# TriDrone_mini_v1.net
KiCad netlist of a schematic drawn in EAGLE
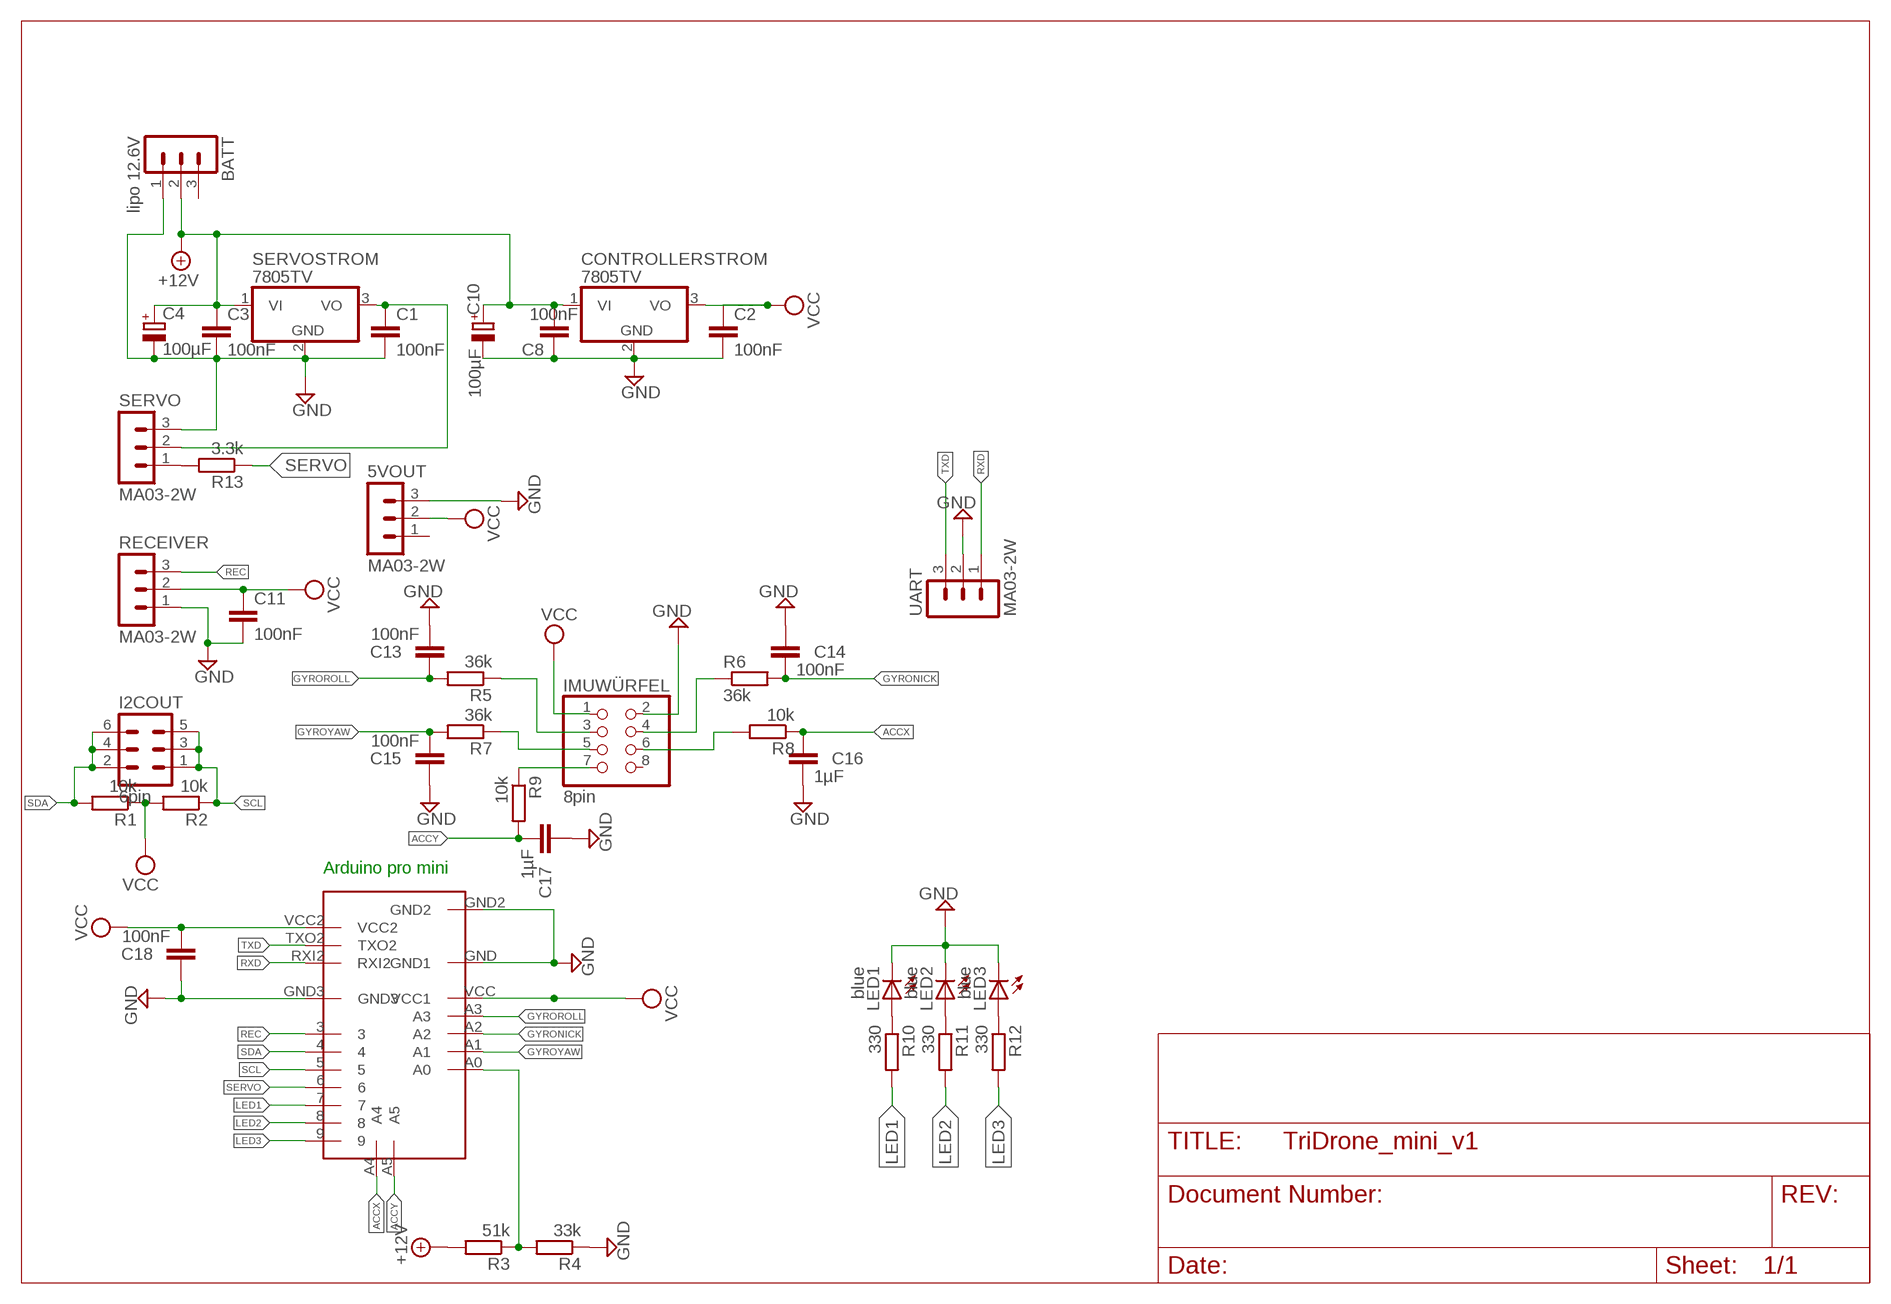
[diagram p0: schematic, sheet 1]

(export (version "E")
  (design (tool "Eeschema 10.0.6"))
  (components
    (comp (ref "5VOUT")
      (value "MA03-2W")
      (footprint "eagle-import:MA03-1")
      (libsource (lib "eagle-import") (part "MA03-1"))
    )
    (comp (ref "BATT")
      (value "lipo 12.6V")
      (footprint "eagle-import:MA03-1")
      (libsource (lib "eagle-import") (part "MA03-1"))
    )
    (comp (ref "C1")
      (value "100nF")
      (footprint "eagle-import:C1206")
      (libsource (lib "eagle-import") (part "C-EUC1206"))
    )
    (comp (ref "C2")
      (value "100nF")
      (footprint "eagle-import:C1206")
      (libsource (lib "eagle-import") (part "C-EUC1206"))
    )
    (comp (ref "C3")
      (value "100nF")
      (footprint "eagle-import:C1206")
      (libsource (lib "eagle-import") (part "C-EUC1206"))
    )
    (comp (ref "C4")
      (value "100µF")
      (footprint "eagle-import:D_7343-31W")
      (libsource (lib "eagle-import") (part "CPOL-EUD/7343-31W"))
    )
    (comp (ref "C8")
      (value "100nF")
      (footprint "eagle-import:C1206")
      (libsource (lib "eagle-import") (part "C-EUC1206"))
    )
    (comp (ref "C10")
      (value "100µF")
      (footprint "eagle-import:D_7343-31W")
      (libsource (lib "eagle-import") (part "CPOL-EUD/7343-31W"))
    )
    (comp (ref "C11")
      (value "100nF")
      (footprint "eagle-import:C1206")
      (libsource (lib "eagle-import") (part "C-EUC1206"))
    )
    (comp (ref "C13")
      (value "100nF")
      (footprint "eagle-import:C1206")
      (libsource (lib "eagle-import") (part "C-EUC1206"))
    )
    (comp (ref "C14")
      (value "100nF")
      (footprint "eagle-import:C1206")
      (libsource (lib "eagle-import") (part "C-EUC1206"))
    )
    (comp (ref "C15")
      (value "100nF")
      (footprint "eagle-import:C1206")
      (libsource (lib "eagle-import") (part "C-EUC1206"))
    )
    (comp (ref "C16")
      (value "1µF")
      (footprint "eagle-import:C1206")
      (libsource (lib "eagle-import") (part "C-EUC1206"))
    )
    (comp (ref "C17")
      (value "1µF")
      (footprint "eagle-import:C1206")
      (libsource (lib "eagle-import") (part "C-EUC1206"))
    )
    (comp (ref "C18")
      (value "100nF")
      (footprint "eagle-import:C1206")
      (libsource (lib "eagle-import") (part "C-EUC1206"))
    )
    (comp (ref "CONTROLLERSTROM")
      (value "7805TV")
      (footprint "eagle-import:TO220V")
      (libsource (lib "eagle-import") (part "78TV05"))
    )
    (comp (ref "I2COUT")
      (value "6pin")
      (footprint "eagle-import:MA07-2W")
      (libsource (lib "eagle-import") (part "MA07-2W"))
    )
    (comp (ref "IMUWÜRFEL")
      (value "8pin")
      (footprint "eagle-import:2X04")
      (libsource (lib "eagle-import") (part "PINHD-2X4"))
    )
    (comp (ref "LED1")
      (value "blue")
      (footprint "eagle-import:LED3MM")
      (libsource (lib "eagle-import") (part "LED3MM"))
    )
    (comp (ref "LED2")
      (value "blue")
      (footprint "eagle-import:LED3MM")
      (libsource (lib "eagle-import") (part "LED3MM"))
    )
    (comp (ref "LED3")
      (value "blue")
      (footprint "eagle-import:LED3MM")
      (libsource (lib "eagle-import") (part "LED3MM"))
    )
    (comp (ref "R1")
      (value "10k")
      (footprint "eagle-import:R1206")
      (libsource (lib "eagle-import") (part "R-EU_R1206"))
    )
    (comp (ref "R2")
      (value "10k")
      (footprint "eagle-import:R1206")
      (libsource (lib "eagle-import") (part "R-EU_R1206"))
    )
    (comp (ref "R3")
      (value "51k")
      (footprint "eagle-import:R1206")
      (libsource (lib "eagle-import") (part "R-EU_R1206"))
    )
    (comp (ref "R4")
      (value "33k")
      (footprint "eagle-import:R1206")
      (libsource (lib "eagle-import") (part "R-EU_R1206"))
    )
    (comp (ref "R5")
      (value "36k")
      (footprint "eagle-import:R1206")
      (libsource (lib "eagle-import") (part "R-EU_R1206"))
    )
    (comp (ref "R6")
      (value "36k")
      (footprint "eagle-import:R1206")
      (libsource (lib "eagle-import") (part "R-EU_R1206"))
    )
    (comp (ref "R7")
      (value "36k")
      (footprint "eagle-import:R1206")
      (libsource (lib "eagle-import") (part "R-EU_R1206"))
    )
    (comp (ref "R8")
      (value "10k")
      (footprint "eagle-import:R1206")
      (libsource (lib "eagle-import") (part "R-EU_R1206"))
    )
    (comp (ref "R9")
      (value "10k")
      (footprint "eagle-import:R1206")
      (libsource (lib "eagle-import") (part "R-EU_R1206"))
    )
    (comp (ref "R10")
      (value "330")
      (footprint "eagle-import:R1206")
      (libsource (lib "eagle-import") (part "R-EU_R1206"))
    )
    (comp (ref "R11")
      (value "330")
      (footprint "eagle-import:R1206")
      (libsource (lib "eagle-import") (part "R-EU_R1206"))
    )
    (comp (ref "R12")
      (value "330")
      (footprint "eagle-import:R1206")
      (libsource (lib "eagle-import") (part "R-EU_R1206"))
    )
    (comp (ref "R13")
      (value "3.3k")
      (footprint "eagle-import:R1206")
      (libsource (lib "eagle-import") (part "R-EU_R1206"))
    )
    (comp (ref "RECEIVER")
      (value "MA03-2W")
      (footprint "eagle-import:MA03-1")
      (libsource (lib "eagle-import") (part "MA03-1"))
    )
    (comp (ref "SERVO")
      (value "MA03-2W")
      (footprint "eagle-import:MA03-1")
      (libsource (lib "eagle-import") (part "MA03-1"))
    )
    (comp (ref "SERVOSTROM")
      (value "7805TV")
      (footprint "eagle-import:TO220V")
      (libsource (lib "eagle-import") (part "78TV05"))
    )
    (comp (ref "U$1")
      (value "ARDUINOMINIPRO")
      (footprint "eagle-import:1X12")
      (libsource (lib "eagle-import") (part "ARDUINOMINIPRO"))
    )
    (comp (ref "UART")
      (value "MA03-2W")
      (footprint "eagle-import:MA03-1")
      (libsource (lib "eagle-import") (part "MA03-1"))
    )
  )
  (nets
    (net (code "1") (name "+12V") (class "Default")
      (node (ref "BATT") (pin "2") (pinfunction "2_2") (pintype "passive"))
      (node (ref "C10") (pin "+") (pinfunction "+_+") (pintype "passive"))
      (node (ref "C3") (pin "1") (pinfunction "1_1") (pintype "passive"))
      (node (ref "C4") (pin "+") (pinfunction "+_+") (pintype "passive"))
      (node (ref "C8") (pin "2") (pinfunction "2_2") (pintype "passive"))
      (node (ref "CONTROLLERSTROM") (pin "1") (pinfunction "VI_1") (pintype "input"))
      (node (ref "R3") (pin "2") (pinfunction "2_2") (pintype "passive"))
      (node (ref "SERVOSTROM") (pin "1") (pinfunction "VI_1") (pintype "input"))
    )
    (net (code "2") (name "ACCX") (class "Default")
      (node (ref "C16") (pin "1") (pinfunction "1_1") (pintype "passive"))
      (node (ref "R8") (pin "1") (pinfunction "1_1") (pintype "passive"))
      (node (ref "U$1") (pin "A4") (pinfunction "A4_A4") (pintype "bidirectional"))
    )
    (net (code "3") (name "ACCY") (class "Default")
      (node (ref "C17") (pin "2") (pinfunction "2_2") (pintype "passive"))
      (node (ref "R9") (pin "2") (pinfunction "2_2") (pintype "passive"))
      (node (ref "U$1") (pin "A5") (pinfunction "A5_A5") (pintype "bidirectional"))
    )
    (net (code "4") (name "GND") (class "Default")
      (node (ref "5VOUT") (pin "3") (pinfunction "3_3") (pintype "passive"))
      (node (ref "BATT") (pin "1") (pinfunction "1_1") (pintype "passive"))
      (node (ref "C1") (pin "2") (pinfunction "2_2") (pintype "passive"))
      (node (ref "C10") (pin "-") (pinfunction "-_-") (pintype "passive"))
      (node (ref "C11") (pin "2") (pinfunction "2_2") (pintype "passive"))
      (node (ref "C13") (pin "2") (pinfunction "2_2") (pintype "passive"))
      (node (ref "C14") (pin "1") (pinfunction "1_1") (pintype "passive"))
      (node (ref "C15") (pin "1") (pinfunction "1_1") (pintype "passive"))
      (node (ref "C16") (pin "2") (pinfunction "2_2") (pintype "passive"))
      (node (ref "C17") (pin "1") (pinfunction "1_1") (pintype "passive"))
      (node (ref "C18") (pin "1") (pinfunction "1_1") (pintype "passive"))
      (node (ref "C2") (pin "2") (pinfunction "2_2") (pintype "passive"))
      (node (ref "C3") (pin "2") (pinfunction "2_2") (pintype "passive"))
      (node (ref "C4") (pin "-") (pinfunction "-_-") (pintype "passive"))
      (node (ref "C8") (pin "1") (pinfunction "1_1") (pintype "passive"))
      (node (ref "CONTROLLERSTROM") (pin "2") (pinfunction "GND_2") (pintype "passive"))
      (node (ref "IMUWÜRFEL") (pin "2") (pinfunction "2_2") (pintype "passive"))
      (node (ref "LED1") (pin "K") (pinfunction "C_K") (pintype "passive"))
      (node (ref "LED2") (pin "K") (pinfunction "C_K") (pintype "passive"))
      (node (ref "LED3") (pin "K") (pinfunction "C_K") (pintype "passive"))
      (node (ref "R4") (pin "1") (pinfunction "1_1") (pintype "passive"))
      (node (ref "RECEIVER") (pin "1") (pinfunction "1_1") (pintype "passive"))
      (node (ref "SERVO") (pin "3") (pinfunction "3_3") (pintype "passive"))
      (node (ref "SERVOSTROM") (pin "2") (pinfunction "GND_2") (pintype "passive"))
      (node (ref "U$1") (pin "GND") (pinfunction "GND1_GND") (pintype "bidirectional"))
      (node (ref "U$1") (pin "GND2") (pinfunction "GND2_GND2") (pintype "bidirectional"))
      (node (ref "U$1") (pin "GND3") (pinfunction "GND3_GND3") (pintype "bidirectional"))
      (node (ref "UART") (pin "2") (pinfunction "2_2") (pintype "passive"))
    )
    (net (code "5") (name "GYRONICK") (class "Default")
      (node (ref "C14") (pin "2") (pinfunction "2_2") (pintype "passive"))
      (node (ref "R6") (pin "2") (pinfunction "2_2") (pintype "passive"))
      (node (ref "U$1") (pin "A2") (pinfunction "A2_A2") (pintype "bidirectional"))
    )
    (net (code "6") (name "GYROROLL") (class "Default")
      (node (ref "C13") (pin "1") (pinfunction "1_1") (pintype "passive"))
      (node (ref "R5") (pin "2") (pinfunction "2_2") (pintype "passive"))
      (node (ref "U$1") (pin "A3") (pinfunction "A3_A3") (pintype "bidirectional"))
    )
    (net (code "7") (name "GYROYAW") (class "Default")
      (node (ref "C15") (pin "2") (pinfunction "2_2") (pintype "passive"))
      (node (ref "R7") (pin "2") (pinfunction "2_2") (pintype "passive"))
      (node (ref "U$1") (pin "A1") (pinfunction "A1_A1") (pintype "bidirectional"))
    )
    (net (code "8") (name "LED1") (class "Default")
      (node (ref "R10") (pin "2") (pinfunction "2_2") (pintype "passive"))
      (node (ref "U$1") (pin "7") (pinfunction "7_7") (pintype "bidirectional"))
    )
    (net (code "9") (name "LED2") (class "Default")
      (node (ref "R11") (pin "2") (pinfunction "2_2") (pintype "passive"))
      (node (ref "U$1") (pin "8") (pinfunction "8_8") (pintype "bidirectional"))
    )
    (net (code "10") (name "LED3") (class "Default")
      (node (ref "R12") (pin "2") (pinfunction "2_2") (pintype "passive"))
      (node (ref "U$1") (pin "9") (pinfunction "9_9") (pintype "bidirectional"))
    )
    (net (code "11") (name "Net-(IMUWÜRFEL-Pad3)") (class "Default")
      (node (ref "IMUWÜRFEL") (pin "3") (pinfunction "3_3") (pintype "passive"))
      (node (ref "R5") (pin "1") (pinfunction "1_1") (pintype "passive"))
    )
    (net (code "12") (name "Net-(IMUWÜRFEL-Pad4)") (class "Default")
      (node (ref "IMUWÜRFEL") (pin "4") (pinfunction "4_4") (pintype "passive"))
      (node (ref "R6") (pin "1") (pinfunction "1_1") (pintype "passive"))
    )
    (net (code "13") (name "Net-(IMUWÜRFEL-Pad5)") (class "Default")
      (node (ref "IMUWÜRFEL") (pin "5") (pinfunction "5_5") (pintype "passive"))
      (node (ref "R7") (pin "1") (pinfunction "1_1") (pintype "passive"))
    )
    (net (code "14") (name "Net-(IMUWÜRFEL-Pad6)") (class "Default")
      (node (ref "IMUWÜRFEL") (pin "6") (pinfunction "6_6") (pintype "passive"))
      (node (ref "R8") (pin "2") (pinfunction "2_2") (pintype "passive"))
    )
    (net (code "15") (name "Net-(IMUWÜRFEL-Pad7)") (class "Default")
      (node (ref "IMUWÜRFEL") (pin "7") (pinfunction "7_7") (pintype "passive"))
      (node (ref "R9") (pin "1") (pinfunction "1_1") (pintype "passive"))
    )
    (net (code "16") (name "Net-(LED1-PadA)") (class "Default")
      (node (ref "LED1") (pin "A") (pinfunction "A_A") (pintype "passive"))
      (node (ref "R10") (pin "1") (pinfunction "1_1") (pintype "passive"))
    )
    (net (code "17") (name "Net-(LED2-PadA)") (class "Default")
      (node (ref "LED2") (pin "A") (pinfunction "A_A") (pintype "passive"))
      (node (ref "R11") (pin "1") (pinfunction "1_1") (pintype "passive"))
    )
    (net (code "18") (name "Net-(LED3-PadA)") (class "Default")
      (node (ref "LED3") (pin "A") (pinfunction "A_A") (pintype "passive"))
      (node (ref "R12") (pin "1") (pinfunction "1_1") (pintype "passive"))
    )
    (net (code "19") (name "Net-(R3-Pad1)") (class "Default")
      (node (ref "R3") (pin "1") (pinfunction "1_1") (pintype "passive"))
      (node (ref "R4") (pin "2") (pinfunction "2_2") (pintype "passive"))
      (node (ref "U$1") (pin "A0") (pinfunction "A0_A0") (pintype "bidirectional"))
    )
    (net (code "20") (name "Net-(R13-Pad2)") (class "Default")
      (node (ref "R13") (pin "2") (pinfunction "2_2") (pintype "passive"))
      (node (ref "SERVO") (pin "1") (pinfunction "1_1") (pintype "passive"))
    )
    (net (code "21") (name "Net-(SERVOSTROM-VO)") (class "Default")
      (node (ref "C1") (pin "1") (pinfunction "1_1") (pintype "passive"))
      (node (ref "SERVO") (pin "2") (pinfunction "2_2") (pintype "passive"))
      (node (ref "SERVOSTROM") (pin "3") (pinfunction "VO_3") (pintype "passive"))
    )
    (net (code "22") (name "REC") (class "Default")
      (node (ref "RECEIVER") (pin "3") (pinfunction "3_3") (pintype "passive"))
      (node (ref "U$1") (pin "3") (pinfunction "3_3") (pintype "bidirectional"))
    )
    (net (code "23") (name "RXD") (class "Default")
      (node (ref "U$1") (pin "RXI2") (pinfunction "RXI2_RXI2") (pintype "bidirectional"))
      (node (ref "UART") (pin "1") (pinfunction "1_1") (pintype "passive"))
    )
    (net (code "24") (name "SCL") (class "Default")
      (node (ref "I2COUT") (pin "1") (pinfunction "1_1") (pintype "passive"))
      (node (ref "I2COUT") (pin "3") (pinfunction "3_3") (pintype "passive"))
      (node (ref "I2COUT") (pin "5") (pinfunction "5_5") (pintype "passive"))
      (node (ref "R2") (pin "1") (pinfunction "1_1") (pintype "passive"))
      (node (ref "U$1") (pin "5") (pinfunction "5_5") (pintype "bidirectional"))
    )
    (net (code "25") (name "SDA") (class "Default")
      (node (ref "I2COUT") (pin "2") (pinfunction "2_2") (pintype "passive"))
      (node (ref "I2COUT") (pin "4") (pinfunction "4_4") (pintype "passive"))
      (node (ref "I2COUT") (pin "6") (pinfunction "6_6") (pintype "passive"))
      (node (ref "R1") (pin "2") (pinfunction "2_2") (pintype "passive"))
      (node (ref "U$1") (pin "4") (pinfunction "4_4") (pintype "bidirectional"))
    )
    (net (code "26") (name "SERVO") (class "Default")
      (node (ref "R13") (pin "1") (pinfunction "1_1") (pintype "passive"))
      (node (ref "U$1") (pin "6") (pinfunction "6_6") (pintype "bidirectional"))
    )
    (net (code "27") (name "TXD") (class "Default")
      (node (ref "U$1") (pin "TXO2") (pinfunction "TXO2_TXO2") (pintype "bidirectional"))
      (node (ref "UART") (pin "3") (pinfunction "3_3") (pintype "passive"))
    )
    (net (code "28") (name "VCC") (class "Default")
      (node (ref "5VOUT") (pin "2") (pinfunction "2_2") (pintype "passive"))
      (node (ref "C11") (pin "1") (pinfunction "1_1") (pintype "passive"))
      (node (ref "C18") (pin "2") (pinfunction "2_2") (pintype "passive"))
      (node (ref "C2") (pin "1") (pinfunction "1_1") (pintype "passive"))
      (node (ref "CONTROLLERSTROM") (pin "3") (pinfunction "VO_3") (pintype "passive"))
      (node (ref "IMUWÜRFEL") (pin "1") (pinfunction "1_1") (pintype "passive"))
      (node (ref "R1") (pin "1") (pinfunction "1_1") (pintype "passive"))
      (node (ref "R2") (pin "2") (pinfunction "2_2") (pintype "passive"))
      (node (ref "RECEIVER") (pin "2") (pinfunction "2_2") (pintype "passive"))
      (node (ref "U$1") (pin "VCC") (pinfunction "VCC1_VCC") (pintype "bidirectional"))
      (node (ref "U$1") (pin "VCC2") (pinfunction "VCC2_VCC2") (pintype "bidirectional"))
    )
    (net (code "29") (name "unconnected-(5VOUT-Pad1)") (class "Default")
      (node (ref "5VOUT") (pin "1") (pinfunction "1_1") (pintype "passive"))
    )
    (net (code "30") (name "unconnected-(BATT-Pad3)") (class "Default")
      (node (ref "BATT") (pin "3") (pinfunction "3_3") (pintype "passive"))
    )
    (net (code "31") (name "unconnected-(IMUWÜRFEL-Pad8)") (class "Default")
      (node (ref "IMUWÜRFEL") (pin "8") (pinfunction "8_8") (pintype "passive"))
    )
  )
)
